# RTC.net
KiCad netlist of a schematic drawn in EAGLE
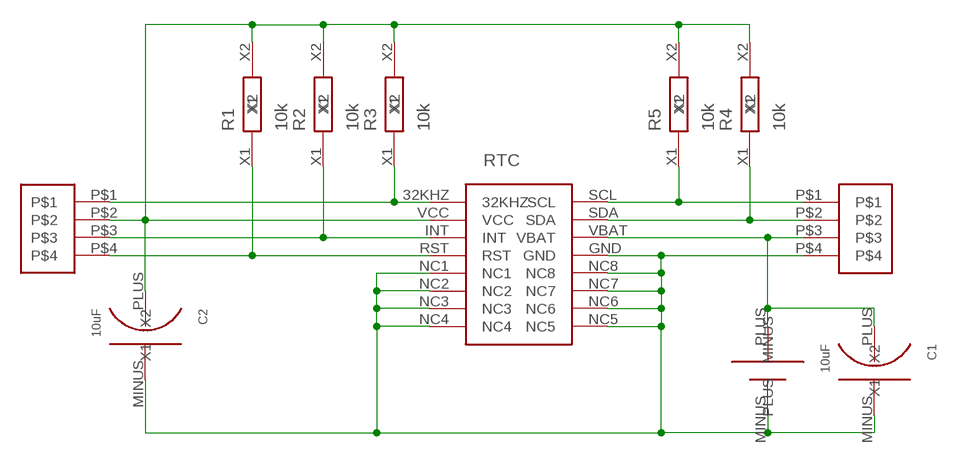
[diagram p0: schematic, sheet 1]

(export (version "E")
  (design (tool "Eeschema 10.0.6"))
  (components
    (comp (ref "C1")
      (value "10uF")
      (footprint "eagle-import:C_SMD_TA_A")
      (libsource (lib "eagle-import") (part "C_SMD_TA_A"))
    )
    (comp (ref "C2")
      (value "10uF")
      (footprint "eagle-import:C_SMD_TA_A")
      (libsource (lib "eagle-import") (part "C_SMD_TA_A"))
    )
    (comp (ref "R1")
      (value "10k")
      (footprint "eagle-import:SMD_2.1X1.25")
      (libsource (lib "eagle-import") (part "R_SMD_2.1X1.25"))
    )
    (comp (ref "R2")
      (value "10k")
      (footprint "eagle-import:SMD_2.1X1.25")
      (libsource (lib "eagle-import") (part "R_SMD_2.1X1.25"))
    )
    (comp (ref "R3")
      (value "10k")
      (footprint "eagle-import:SMD_2.1X1.25")
      (libsource (lib "eagle-import") (part "R_SMD_2.1X1.25"))
    )
    (comp (ref "R4")
      (value "10k")
      (footprint "eagle-import:SMD_2.1X1.25")
      (libsource (lib "eagle-import") (part "R_SMD_2.1X1.25"))
    )
    (comp (ref "R5")
      (value "10k")
      (footprint "eagle-import:SMD_2.1X1.25")
      (libsource (lib "eagle-import") (part "R_SMD_2.1X1.25"))
    )
    (comp (ref "RTC")
      (value "RTC_DS3231")
      (footprint "eagle-import:RTC_DS3231")
      (libsource (lib "eagle-import") (part "RTC_DS3231"))
    )
    (comp (ref "U$2")
      (value "VBAT")
      (footprint "eagle-import:VBAT")
      (libsource (lib "eagle-import") (part "VBAT"))
    )
    (comp (ref "U$3")
      (value "4-PIN-NONAME")
      (footprint "eagle-import:4-PIN-NONAME")
      (libsource (lib "eagle-import") (part "4-PIN-NONAME"))
    )
    (comp (ref "U$4")
      (value "4-PIN-NONAME")
      (footprint "eagle-import:4-PIN-NONAME")
      (libsource (lib "eagle-import") (part "4-PIN-NONAME"))
    )
  )
  (nets
    (net (code "1") (name "Net-(C1-X1)") (class "Default")
      (node (ref "C1") (pin "PLUS") (pinfunction "X1_PLUS") (pintype "bidirectional"))
      (node (ref "RTC") (pin "VBAT") (pinfunction "VBAT_VBAT") (pintype "bidirectional"))
      (node (ref "U$2") (pin "PLUS") (pinfunction "PLUS_PLUS") (pintype "bidirectional"))
      (node (ref "U$3") (pin "P$3") (pinfunction "P$3_P$3") (pintype "bidirectional"))
    )
    (net (code "2") (name "Net-(C1-X2)") (class "Default")
      (node (ref "C1") (pin "MINUS") (pinfunction "X2_MINUS") (pintype "bidirectional"))
      (node (ref "C2") (pin "MINUS") (pinfunction "X2_MINUS") (pintype "bidirectional"))
      (node (ref "RTC") (pin "GND") (pinfunction "GND_GND") (pintype "bidirectional"))
      (node (ref "RTC") (pin "NC1") (pinfunction "NC1_NC1") (pintype "bidirectional"))
      (node (ref "RTC") (pin "NC2") (pinfunction "NC2_NC2") (pintype "bidirectional"))
      (node (ref "RTC") (pin "NC3") (pinfunction "NC3_NC3") (pintype "bidirectional"))
      (node (ref "RTC") (pin "NC4") (pinfunction "NC4_NC4") (pintype "bidirectional"))
      (node (ref "RTC") (pin "NC5") (pinfunction "NC5_NC5") (pintype "bidirectional"))
      (node (ref "RTC") (pin "NC6") (pinfunction "NC6_NC6") (pintype "bidirectional"))
      (node (ref "RTC") (pin "NC7") (pinfunction "NC7_NC7") (pintype "bidirectional"))
      (node (ref "RTC") (pin "NC8") (pinfunction "NC8_NC8") (pintype "bidirectional"))
      (node (ref "U$2") (pin "MINUS") (pinfunction "MINUS_MINUS") (pintype "bidirectional"))
      (node (ref "U$3") (pin "P$4") (pinfunction "P$4_P$4") (pintype "bidirectional"))
    )
    (net (code "3") (name "Net-(C2-X1)") (class "Default")
      (node (ref "C2") (pin "PLUS") (pinfunction "X1_PLUS") (pintype "bidirectional"))
      (node (ref "R1") (pin "X2") (pinfunction "X2_X2") (pintype "bidirectional"))
      (node (ref "R2") (pin "X2") (pinfunction "X2_X2") (pintype "bidirectional"))
      (node (ref "R3") (pin "X2") (pinfunction "X2_X2") (pintype "bidirectional"))
      (node (ref "R4") (pin "X2") (pinfunction "X2_X2") (pintype "bidirectional"))
      (node (ref "R5") (pin "X2") (pinfunction "X2_X2") (pintype "bidirectional"))
      (node (ref "RTC") (pin "VCC") (pinfunction "VCC_VCC") (pintype "bidirectional"))
      (node (ref "U$4") (pin "P$2") (pinfunction "P$2_P$2") (pintype "bidirectional"))
    )
    (net (code "4") (name "Net-(R1-PadX1)") (class "Default")
      (node (ref "R1") (pin "X1") (pinfunction "X1_X1") (pintype "bidirectional"))
      (node (ref "RTC") (pin "RST") (pinfunction "RST_RST") (pintype "bidirectional"))
      (node (ref "U$4") (pin "P$4") (pinfunction "P$4_P$4") (pintype "bidirectional"))
    )
    (net (code "5") (name "Net-(R2-PadX1)") (class "Default")
      (node (ref "R2") (pin "X1") (pinfunction "X1_X1") (pintype "bidirectional"))
      (node (ref "RTC") (pin "INT") (pinfunction "INT_INT") (pintype "bidirectional"))
      (node (ref "U$4") (pin "P$3") (pinfunction "P$3_P$3") (pintype "bidirectional"))
    )
    (net (code "6") (name "Net-(R3-PadX1)") (class "Default")
      (node (ref "R3") (pin "X1") (pinfunction "X1_X1") (pintype "bidirectional"))
      (node (ref "RTC") (pin "32KHZ") (pinfunction "32KHZ_32KHZ") (pintype "bidirectional"))
      (node (ref "U$4") (pin "P$1") (pinfunction "P$1_P$1") (pintype "bidirectional"))
    )
    (net (code "7") (name "Net-(R4-PadX1)") (class "Default")
      (node (ref "R4") (pin "X1") (pinfunction "X1_X1") (pintype "bidirectional"))
      (node (ref "RTC") (pin "SDA") (pinfunction "SDA_SDA") (pintype "bidirectional"))
      (node (ref "U$3") (pin "P$2") (pinfunction "P$2_P$2") (pintype "bidirectional"))
    )
    (net (code "8") (name "Net-(R5-PadX1)") (class "Default")
      (node (ref "R5") (pin "X1") (pinfunction "X1_X1") (pintype "bidirectional"))
      (node (ref "RTC") (pin "SCL") (pinfunction "SCL_SCL") (pintype "bidirectional"))
      (node (ref "U$3") (pin "P$1") (pinfunction "P$1_P$1") (pintype "bidirectional"))
    )
  )
)
